# aery32.net
KiCad netlist of a schematic drawn in EAGLE
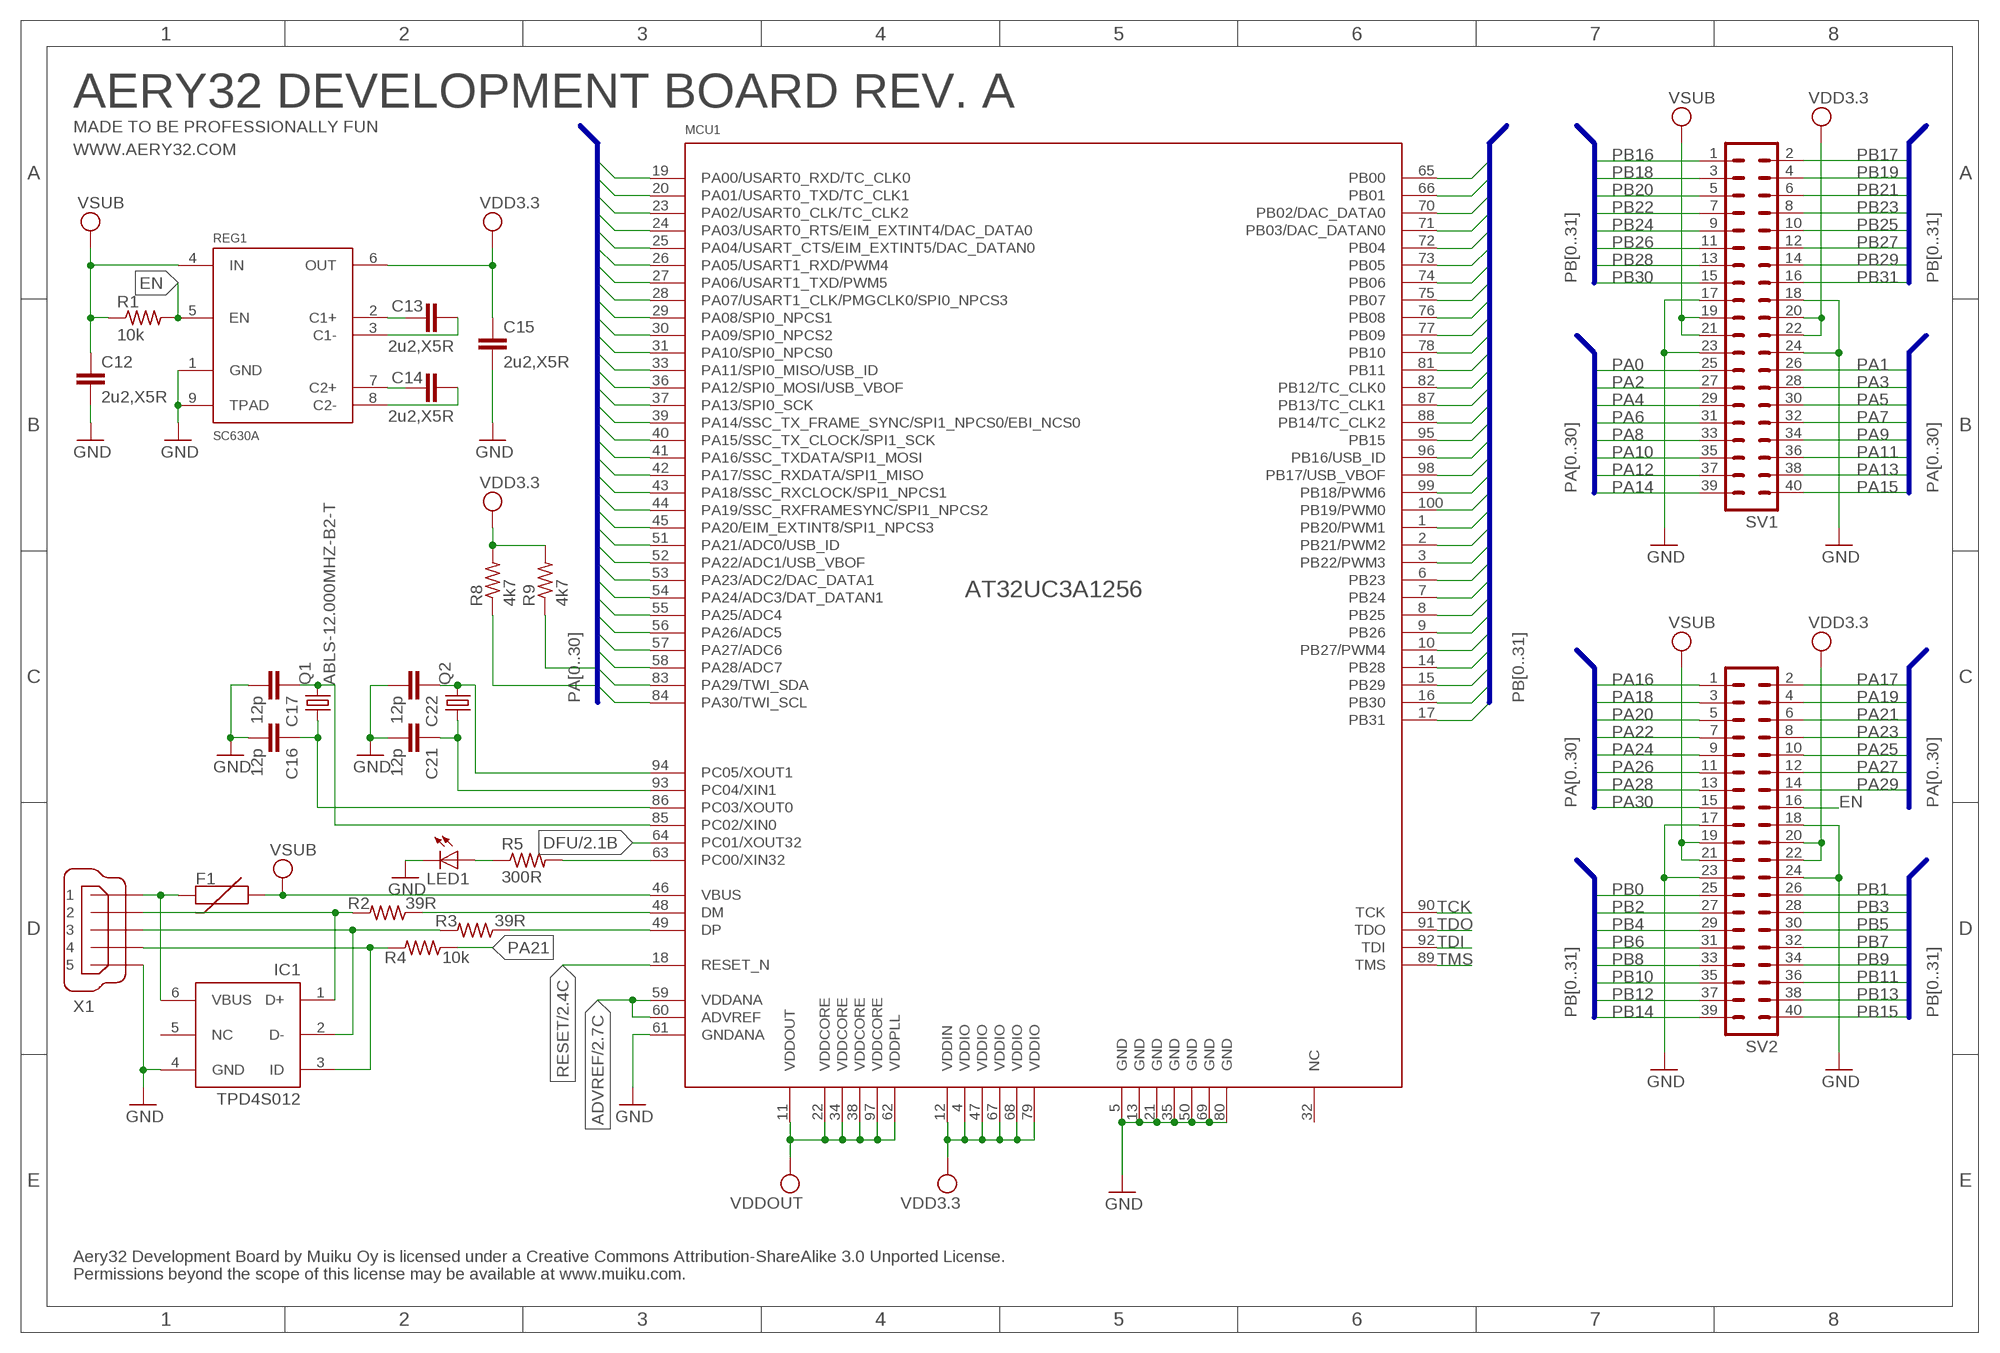
[diagram p0: schematic, sheet 1]
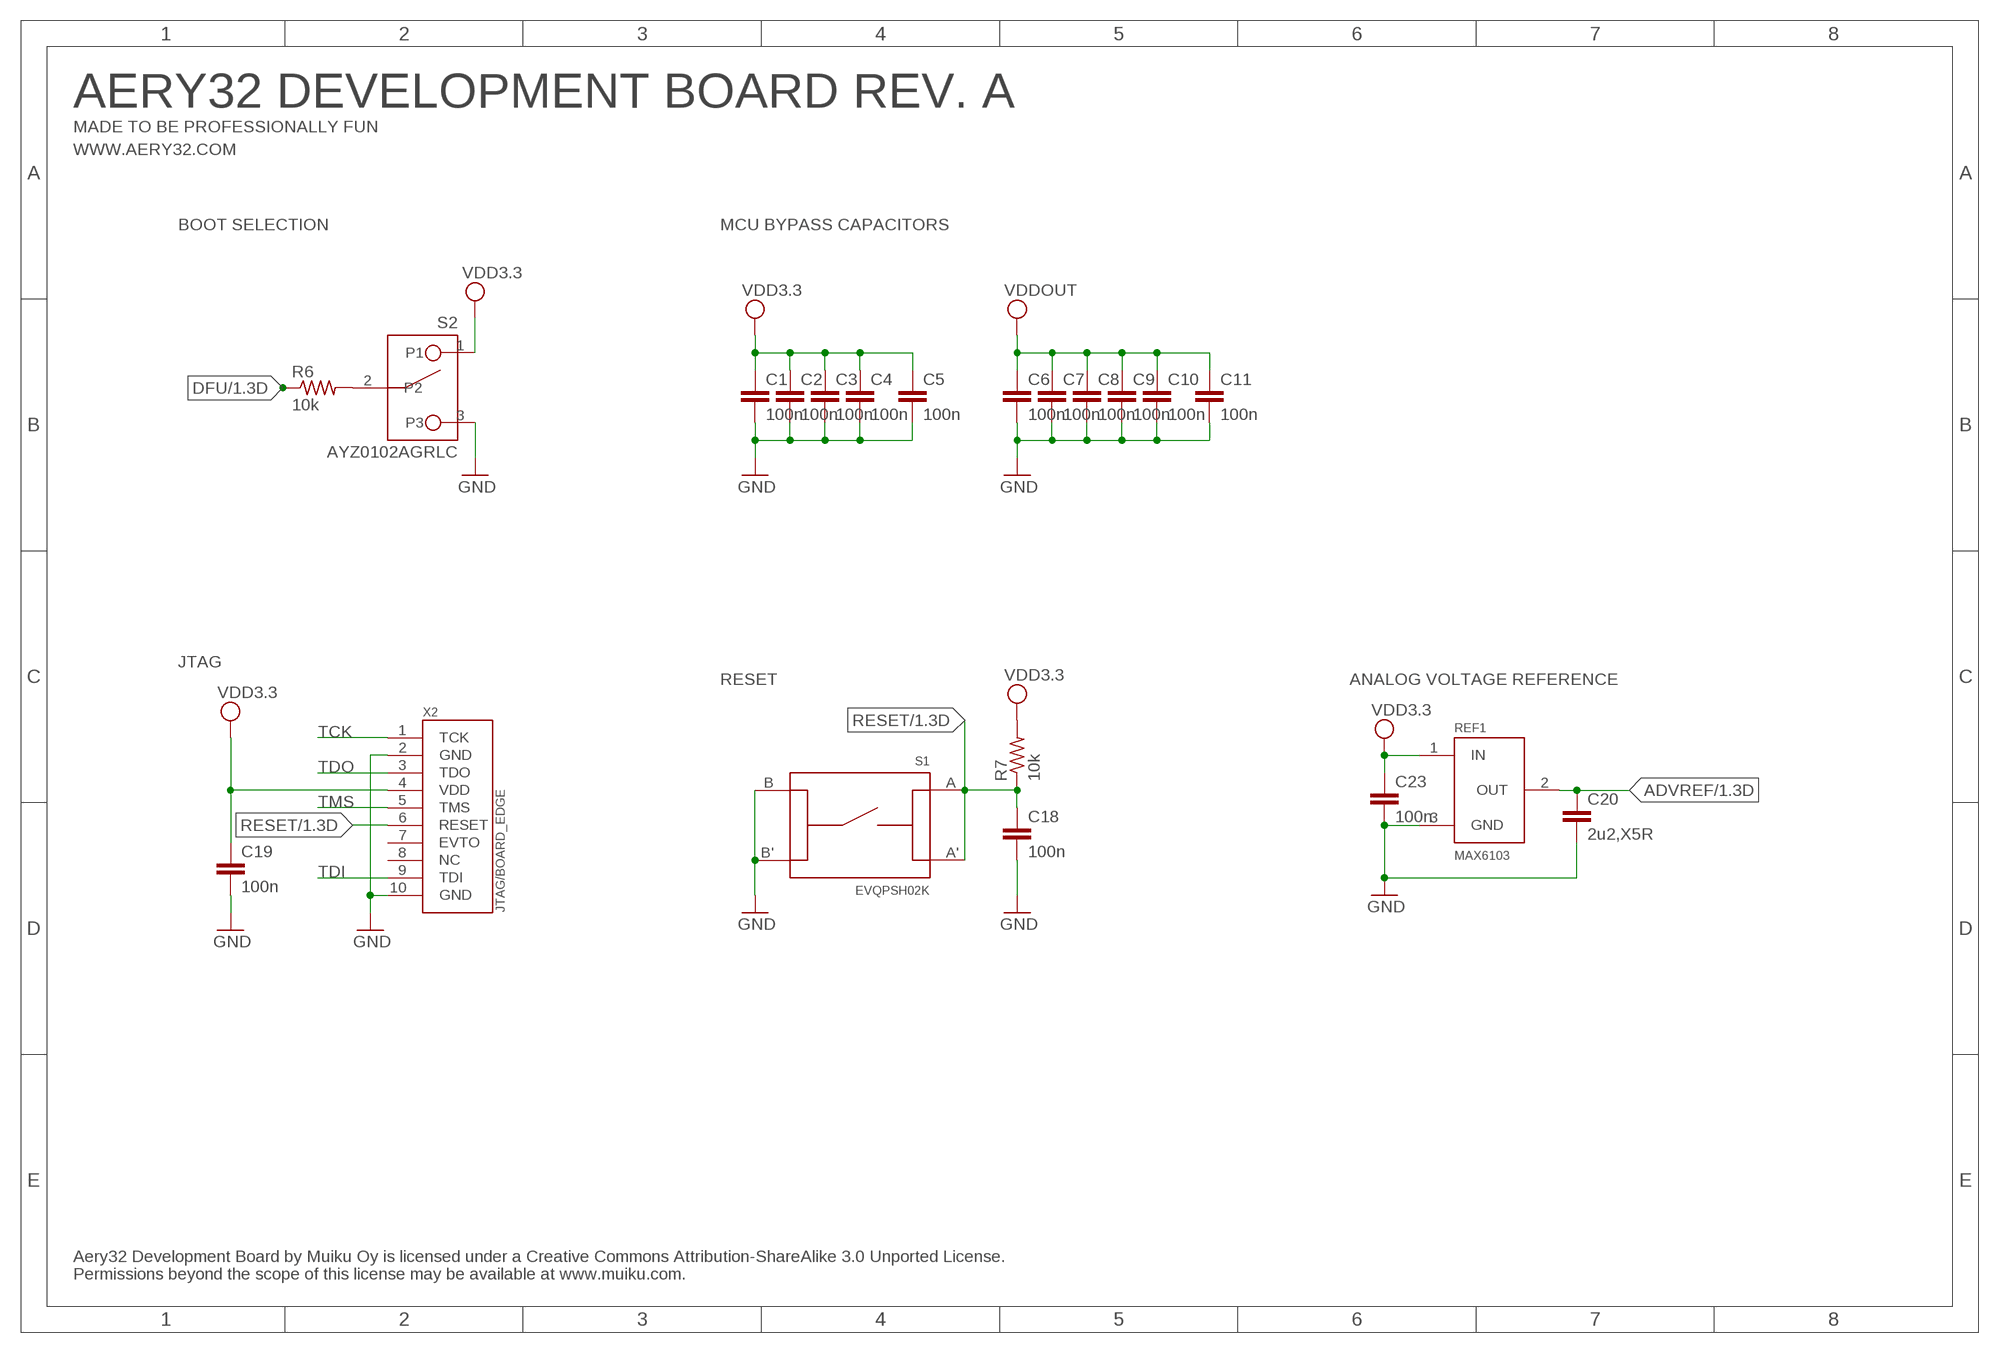
[diagram p1: schematic, sheet 2]

(export (version "E")
  (design (tool "Eeschema 10.0.6"))
  (components
    (comp (ref "C1")
      (value "100n")
      (footprint "eagle-import:C0402")
      (libsource (lib "eagle-import") (part "C-EUC0402"))
    )
    (comp (ref "C2")
      (value "100n")
      (footprint "eagle-import:C0402")
      (libsource (lib "eagle-import") (part "C-EUC0402"))
    )
    (comp (ref "C3")
      (value "100n")
      (footprint "eagle-import:C0402")
      (libsource (lib "eagle-import") (part "C-EUC0402"))
    )
    (comp (ref "C4")
      (value "100n")
      (footprint "eagle-import:C0402")
      (libsource (lib "eagle-import") (part "C-EUC0402"))
    )
    (comp (ref "C5")
      (value "100n")
      (footprint "eagle-import:C0402")
      (libsource (lib "eagle-import") (part "C-EUC0402"))
    )
    (comp (ref "C6")
      (value "100n")
      (footprint "eagle-import:C0402")
      (libsource (lib "eagle-import") (part "C-EUC0402"))
    )
    (comp (ref "C7")
      (value "100n")
      (footprint "eagle-import:C0402")
      (libsource (lib "eagle-import") (part "C-EUC0402"))
    )
    (comp (ref "C8")
      (value "100n")
      (footprint "eagle-import:C0402")
      (libsource (lib "eagle-import") (part "C-EUC0402"))
    )
    (comp (ref "C9")
      (value "100n")
      (footprint "eagle-import:C0402")
      (libsource (lib "eagle-import") (part "C-EUC0402"))
    )
    (comp (ref "C10")
      (value "100n")
      (footprint "eagle-import:C0402")
      (libsource (lib "eagle-import") (part "C-EUC0402"))
    )
    (comp (ref "C11")
      (value "100n")
      (footprint "eagle-import:C0402")
      (libsource (lib "eagle-import") (part "C-EUC0402"))
    )
    (comp (ref "C18")
      (value "100n")
      (footprint "eagle-import:C0402")
      (libsource (lib "eagle-import") (part "C-EUC0402"))
    )
    (comp (ref "C19")
      (value "100n")
      (footprint "eagle-import:C0402")
      (libsource (lib "eagle-import") (part "C-EUC0402"))
    )
    (comp (ref "C20")
      (value "2u2,X5R")
      (footprint "eagle-import:C0402")
      (libsource (lib "eagle-import") (part "C-EUC0402"))
    )
    (comp (ref "C23")
      (value "100n")
      (footprint "eagle-import:C0402")
      (libsource (lib "eagle-import") (part "C-EUC0402"))
    )
    (comp (ref "R6")
      (value "10k")
      (footprint "eagle-import:R0402")
      (libsource (lib "eagle-import") (part "R-US_R0402"))
    )
    (comp (ref "R7")
      (value "10k")
      (footprint "eagle-import:R0402")
      (libsource (lib "eagle-import") (part "R-US_R0402"))
    )
    (comp (ref "REF1")
      (value "MAX6103")
      (footprint "eagle-import:SOT23")
      (libsource (lib "eagle-import") (part "REF3320"))
    )
    (comp (ref "S1")
      (value "EVQPSH02K")
      (footprint "eagle-import:EVQPSH02K")
      (libsource (lib "eagle-import") (part "EVQPSH02K"))
    )
    (comp (ref "S2")
      (value "AYZ0102AGRLC")
      (footprint "eagle-import:AYZ0102AGRLC")
      (libsource (lib "eagle-import") (part "AYZ0102AGRLC"))
    )
    (comp (ref "X2")
      (value "JTAG/BOARD_EDGE")
      (footprint "eagle-import:JTAG_BOARD_EDGE")
      (libsource (lib "eagle-import") (part "JTAG/BOARD_EDGE"))
    )
    (comp (ref "C12")
      (value "2u2,X5R")
      (footprint "eagle-import:C0402")
      (libsource (lib "eagle-import") (part "C-EUC0402"))
    )
    (comp (ref "C13")
      (value "2u2,X5R")
      (footprint "eagle-import:C0402")
      (libsource (lib "eagle-import") (part "C-EUC0402"))
    )
    (comp (ref "C14")
      (value "2u2,X5R")
      (footprint "eagle-import:C0402")
      (libsource (lib "eagle-import") (part "C-EUC0402"))
    )
    (comp (ref "C15")
      (value "2u2,X5R")
      (footprint "eagle-import:C0402")
      (libsource (lib "eagle-import") (part "C-EUC0402"))
    )
    (comp (ref "C16")
      (value "12p")
      (footprint "eagle-import:C0402")
      (libsource (lib "eagle-import") (part "C-EUC0402"))
    )
    (comp (ref "C17")
      (value "12p")
      (footprint "eagle-import:C0402")
      (libsource (lib "eagle-import") (part "C-EUC0402"))
    )
    (comp (ref "C21")
      (value "12p")
      (footprint "eagle-import:C0402")
      (libsource (lib "eagle-import") (part "C-EUC0402"))
    )
    (comp (ref "C22")
      (value "12p")
      (footprint "eagle-import:C0402")
      (libsource (lib "eagle-import") (part "C-EUC0402"))
    )
    (comp (ref "F1")
      (value "PTCSMD")
      (footprint "eagle-import:PTC-1206")
      (libsource (lib "eagle-import") (part "PTCSMD"))
    )
    (comp (ref "IC1")
      (value "TPD4S012")
      (footprint "eagle-import:DRY")
      (libsource (lib "eagle-import") (part "TPD4S012"))
    )
    (comp (ref "LED1")
      (value "LEDCHIPLED_0805")
      (footprint "eagle-import:CHIPLED_0805")
      (libsource (lib "eagle-import") (part "LEDCHIPLED_0805"))
    )
    (comp (ref "MCU1")
      (value "AT32UC3A1256")
      (footprint "eagle-import:TQFP100")
      (fields (field (name "FARNELL") "1841636"))
      (libsource (lib "eagle-import") (part "AT32UC3A1128"))
    )
    (comp (ref "Q1")
      (value "ABLS-12.000MHZ-B2-T")
      (footprint "eagle-import:HC49UP")
      (libsource (lib "eagle-import") (part "CRYSTALHC49UP"))
    )
    (comp (ref "Q2")
      (value "CRYSTALTC38H")
      (footprint "eagle-import:TC38H")
      (libsource (lib "eagle-import") (part "CRYSTALTC38H"))
    )
    (comp (ref "R1")
      (value "10k")
      (footprint "eagle-import:R0402")
      (libsource (lib "eagle-import") (part "R-US_R0402"))
    )
    (comp (ref "R2")
      (value "39R")
      (footprint "eagle-import:R0402")
      (libsource (lib "eagle-import") (part "R-US_R0402"))
    )
    (comp (ref "R3")
      (value "39R")
      (footprint "eagle-import:R0402")
      (libsource (lib "eagle-import") (part "R-US_R0402"))
    )
    (comp (ref "R4")
      (value "10k")
      (footprint "eagle-import:R0402")
      (libsource (lib "eagle-import") (part "R-US_R0402"))
    )
    (comp (ref "R5")
      (value "300R")
      (footprint "eagle-import:R0402")
      (libsource (lib "eagle-import") (part "R-US_R0402"))
    )
    (comp (ref "R8")
      (value "4k7")
      (footprint "eagle-import:R0402")
      (libsource (lib "eagle-import") (part "R-US_R0402"))
    )
    (comp (ref "R9")
      (value "4k7")
      (footprint "eagle-import:R0402")
      (libsource (lib "eagle-import") (part "R-US_R0402"))
    )
    (comp (ref "REG1")
      (value "SC630A")
      (footprint "eagle-import:MLPD-UT-8")
      (libsource (lib "eagle-import") (part "SC630A"))
    )
    (comp (ref "SV1")
      (value "MA20-2")
      (footprint "eagle-import:MA20-2")
      (libsource (lib "eagle-import") (part "MA20-2"))
    )
    (comp (ref "SV2")
      (value "MA20-2")
      (footprint "eagle-import:MA20-2")
      (libsource (lib "eagle-import") (part "MA20-2"))
    )
    (comp (ref "X1")
      (value "USBMINI-B")
      (footprint "eagle-import:MINIUSB")
      (libsource (lib "eagle-import") (part "MINIUSB"))
    )
  )
  (nets
    (net (code "3") (name "ADVREF") (class "Default")
      (node (ref "C20") (pin "1") (pinfunction "1_1") (pintype "passive"))
      (node (ref "MCU1") (pin "59") (pinfunction "VDDANA_59") (pintype "passive"))
      (node (ref "MCU1") (pin "60") (pinfunction "ADVREF_60") (pintype "passive"))
      (node (ref "REF1") (pin "2") (pinfunction "OUT_2") (pintype "passive"))
    )
    (net (code "4") (name "DFU") (class "Default")
      (node (ref "MCU1") (pin "64") (pinfunction "PC01/XOUT32_64") (pintype "bidirectional"))
      (node (ref "R6") (pin "1") (pinfunction "1_1") (pintype "passive"))
    )
    (net (code "5") (name "EN") (class "Default")
      (node (ref "R1") (pin "2") (pinfunction "2_2") (pintype "passive"))
      (node (ref "REG1") (pin "5") (pinfunction "EN_5") (pintype "input"))
      (node (ref "SV2") (pin "16") (pinfunction "16_16") (pintype "passive"))
    )
    (net (code "6") (name "GND") (class "Default")
      (node (ref "C1") (pin "2") (pinfunction "2_2") (pintype "passive"))
      (node (ref "C10") (pin "2") (pinfunction "2_2") (pintype "passive"))
      (node (ref "C11") (pin "2") (pinfunction "2_2") (pintype "passive"))
      (node (ref "C12") (pin "2") (pinfunction "2_2") (pintype "passive"))
      (node (ref "C15") (pin "2") (pinfunction "2_2") (pintype "passive"))
      (node (ref "C16") (pin "2") (pinfunction "2_2") (pintype "passive"))
      (node (ref "C17") (pin "2") (pinfunction "2_2") (pintype "passive"))
      (node (ref "C18") (pin "2") (pinfunction "2_2") (pintype "passive"))
      (node (ref "C19") (pin "2") (pinfunction "2_2") (pintype "passive"))
      (node (ref "C2") (pin "2") (pinfunction "2_2") (pintype "passive"))
      (node (ref "C20") (pin "2") (pinfunction "2_2") (pintype "passive"))
      (node (ref "C21") (pin "2") (pinfunction "2_2") (pintype "passive"))
      (node (ref "C22") (pin "2") (pinfunction "2_2") (pintype "passive"))
      (node (ref "C23") (pin "2") (pinfunction "2_2") (pintype "passive"))
      (node (ref "C3") (pin "2") (pinfunction "2_2") (pintype "passive"))
      (node (ref "C4") (pin "2") (pinfunction "2_2") (pintype "passive"))
      (node (ref "C5") (pin "2") (pinfunction "2_2") (pintype "passive"))
      (node (ref "C6") (pin "2") (pinfunction "2_2") (pintype "passive"))
      (node (ref "C7") (pin "2") (pinfunction "2_2") (pintype "passive"))
      (node (ref "C8") (pin "2") (pinfunction "2_2") (pintype "passive"))
      (node (ref "C9") (pin "2") (pinfunction "2_2") (pintype "passive"))
      (node (ref "IC1") (pin "4") (pinfunction "GND_4") (pintype "passive"))
      (node (ref "LED1") (pin "C") (pinfunction "C_C") (pintype "passive"))
      (node (ref "MCU1") (pin "13") (pinfunction "GND_13") (pintype "power_in"))
      (node (ref "MCU1") (pin "21") (pinfunction "GND_21") (pintype "power_in"))
      (node (ref "MCU1") (pin "35") (pinfunction "GND_35") (pintype "bidirectional"))
      (node (ref "MCU1") (pin "5") (pinfunction "GND_5") (pintype "power_in"))
      (node (ref "MCU1") (pin "50") (pinfunction "GND_50") (pintype "bidirectional"))
      (node (ref "MCU1") (pin "61") (pinfunction "GNDANA_61") (pintype "passive"))
      (node (ref "MCU1") (pin "69") (pinfunction "GND_69") (pintype "power_in"))
      (node (ref "MCU1") (pin "80") (pinfunction "GND_80") (pintype "power_in"))
      (node (ref "REF1") (pin "3") (pinfunction "GND_3") (pintype "passive"))
      (node (ref "REG1") (pin "1") (pinfunction "GND_1") (pintype "passive"))
      (node (ref "REG1") (pin "9") (pinfunction "TPAD_9") (pintype "passive"))
      (node (ref "S1") (pin "B") (pinfunction "B_B") (pintype "passive"))
      (node (ref "S1") (pin "B'") (pinfunction "B'_B'") (pintype "passive"))
      (node (ref "S2") (pin "3") (pinfunction "P3_3") (pintype "passive"))
      (node (ref "SV1") (pin "17") (pinfunction "17_17") (pintype "passive"))
      (node (ref "SV1") (pin "18") (pinfunction "18_18") (pintype "passive"))
      (node (ref "SV1") (pin "23") (pinfunction "23_23") (pintype "passive"))
      (node (ref "SV1") (pin "24") (pinfunction "24_24") (pintype "passive"))
      (node (ref "SV2") (pin "17") (pinfunction "17_17") (pintype "passive"))
      (node (ref "SV2") (pin "18") (pinfunction "18_18") (pintype "passive"))
      (node (ref "SV2") (pin "23") (pinfunction "23_23") (pintype "passive"))
      (node (ref "SV2") (pin "24") (pinfunction "24_24") (pintype "passive"))
      (node (ref "X1") (pin "5") (pinfunction "5_5") (pintype "passive"))
      (node (ref "X2") (pin "10") (pinfunction "GND_10") (pintype "power_in"))
      (node (ref "X2") (pin "2") (pinfunction "GND_2") (pintype "power_in"))
    )
    (net (code "7") (name "Net-(IC1-D+)") (class "Default")
      (node (ref "IC1") (pin "1") (pinfunction "D+_1") (pintype "passive"))
      (node (ref "R2") (pin "2") (pinfunction "2_2") (pintype "passive"))
      (node (ref "X1") (pin "2") (pinfunction "2_2") (pintype "passive"))
    )
    (net (code "8") (name "Net-(IC1-D-)") (class "Default")
      (node (ref "IC1") (pin "2") (pinfunction "D-_2") (pintype "passive"))
      (node (ref "R3") (pin "2") (pinfunction "2_2") (pintype "passive"))
      (node (ref "X1") (pin "3") (pinfunction "3_3") (pintype "passive"))
    )
    (net (code "9") (name "Net-(IC1-ID)") (class "Default")
      (node (ref "IC1") (pin "3") (pinfunction "ID_3") (pintype "passive"))
      (node (ref "R4") (pin "2") (pinfunction "2_2") (pintype "passive"))
      (node (ref "X1") (pin "4") (pinfunction "4_4") (pintype "passive"))
    )
    (net (code "10") (name "Net-(IC1-VBUS)") (class "Default")
      (node (ref "F1") (pin "2") (pinfunction "2_2") (pintype "bidirectional"))
      (node (ref "IC1") (pin "6") (pinfunction "VBUS_6") (pintype "passive"))
      (node (ref "X1") (pin "1") (pinfunction "1_1") (pintype "passive"))
    )
    (net (code "11") (name "Net-(LED1-PadA)") (class "Default")
      (node (ref "LED1") (pin "A") (pinfunction "A_A") (pintype "passive"))
      (node (ref "R5") (pin "1") (pinfunction "1_1") (pintype "passive"))
    )
    (net (code "12") (name "Net-(MCU1-DM)") (class "Default")
      (node (ref "MCU1") (pin "48") (pinfunction "DM_48") (pintype "bidirectional"))
      (node (ref "R2") (pin "1") (pinfunction "1_1") (pintype "passive"))
    )
    (net (code "13") (name "Net-(MCU1-DP)") (class "Default")
      (node (ref "MCU1") (pin "49") (pinfunction "DP_49") (pintype "bidirectional"))
      (node (ref "R3") (pin "1") (pinfunction "1_1") (pintype "passive"))
    )
    (net (code "14") (name "Net-(MCU1-PC00{slash}XIN32)") (class "Default")
      (node (ref "MCU1") (pin "63") (pinfunction "PC00/XIN32_63") (pintype "bidirectional"))
      (node (ref "R5") (pin "2") (pinfunction "2_2") (pintype "passive"))
    )
    (net (code "15") (name "Net-(MCU1-PC02{slash}XIN0)") (class "Default")
      (node (ref "C17") (pin "1") (pinfunction "1_1") (pintype "passive"))
      (node (ref "MCU1") (pin "85") (pinfunction "PC02/XIN0_85") (pintype "bidirectional"))
      (node (ref "Q1") (pin "2") (pinfunction "2_2") (pintype "passive"))
    )
    (net (code "16") (name "Net-(MCU1-PC03{slash}XOUT0)") (class "Default")
      (node (ref "C16") (pin "1") (pinfunction "1_1") (pintype "passive"))
      (node (ref "MCU1") (pin "86") (pinfunction "PC03/XOUT0_86") (pintype "bidirectional"))
      (node (ref "Q1") (pin "1") (pinfunction "1_1") (pintype "passive"))
    )
    (net (code "17") (name "Net-(MCU1-PC04{slash}XIN1)") (class "Default")
      (node (ref "C21") (pin "1") (pinfunction "1_1") (pintype "passive"))
      (node (ref "MCU1") (pin "93") (pinfunction "PC04/XIN1_93") (pintype "bidirectional"))
      (node (ref "Q2") (pin "1") (pinfunction "1_1") (pintype "passive"))
    )
    (net (code "18") (name "Net-(MCU1-PC05{slash}XOUT1)") (class "Default")
      (node (ref "C22") (pin "1") (pinfunction "1_1") (pintype "passive"))
      (node (ref "MCU1") (pin "94") (pinfunction "PC05/XOUT1_94") (pintype "bidirectional"))
      (node (ref "Q2") (pin "2") (pinfunction "2_2") (pintype "passive"))
    )
    (net (code "19") (name "Net-(REG1-C1+)") (class "Default")
      (node (ref "C13") (pin "1") (pinfunction "1_1") (pintype "passive"))
      (node (ref "REG1") (pin "2") (pinfunction "C1+_2") (pintype "passive"))
    )
    (net (code "20") (name "Net-(REG1-C1-)") (class "Default")
      (node (ref "C13") (pin "2") (pinfunction "2_2") (pintype "passive"))
      (node (ref "REG1") (pin "3") (pinfunction "C1-_3") (pintype "passive"))
    )
    (net (code "21") (name "Net-(REG1-C2+)") (class "Default")
      (node (ref "C14") (pin "1") (pinfunction "1_1") (pintype "passive"))
      (node (ref "REG1") (pin "7") (pinfunction "C2+_7") (pintype "passive"))
    )
    (net (code "22") (name "Net-(REG1-C2-)") (class "Default")
      (node (ref "C14") (pin "2") (pinfunction "2_2") (pintype "passive"))
      (node (ref "REG1") (pin "8") (pinfunction "C2-_8") (pintype "passive"))
    )
    (net (code "23") (name "Net-(S2-P2)") (class "Default")
      (node (ref "R6") (pin "2") (pinfunction "2_2") (pintype "passive"))
      (node (ref "S2") (pin "2") (pinfunction "P2_2") (pintype "passive"))
    )
    (net (code "24") (name "PA0") (class "Default")
      (node (ref "MCU1") (pin "19") (pinfunction "PA00/USART0_RXD/TC_CLK0_19") (pintype "bidirectional"))
      (node (ref "SV1") (pin "25") (pinfunction "25_25") (pintype "passive"))
    )
    (net (code "25") (name "PA1") (class "Default")
      (node (ref "MCU1") (pin "20") (pinfunction "PA01/USART0_TXD/TC_CLK1_20") (pintype "bidirectional"))
      (node (ref "SV1") (pin "26") (pinfunction "26_26") (pintype "passive"))
    )
    (net (code "26") (name "PA2") (class "Default")
      (node (ref "MCU1") (pin "23") (pinfunction "PA02/USART0_CLK/TC_CLK2_23") (pintype "bidirectional"))
      (node (ref "SV1") (pin "27") (pinfunction "27_27") (pintype "passive"))
    )
    (net (code "27") (name "PA3") (class "Default")
      (node (ref "MCU1") (pin "24") (pinfunction "PA03/USART0_RTS/EIM_EXTINT4/DAC_DATA0_24") (pintype "bidirectional"))
      (node (ref "SV1") (pin "28") (pinfunction "28_28") (pintype "passive"))
    )
    (net (code "28") (name "PA4") (class "Default")
      (node (ref "MCU1") (pin "25") (pinfunction "PA04/USART_CTS/EIM_EXTINT5/DAC_DATAN0_25") (pintype "bidirectional"))
      (node (ref "SV1") (pin "29") (pinfunction "29_29") (pintype "passive"))
    )
    (net (code "29") (name "PA5") (class "Default")
      (node (ref "MCU1") (pin "26") (pinfunction "PA05/USART1_RXD/PWM4_26") (pintype "bidirectional"))
      (node (ref "SV1") (pin "30") (pinfunction "30_30") (pintype "passive"))
    )
    (net (code "30") (name "PA6") (class "Default")
      (node (ref "MCU1") (pin "27") (pinfunction "PA06/USART1_TXD/PWM5_27") (pintype "bidirectional"))
      (node (ref "SV1") (pin "31") (pinfunction "31_31") (pintype "passive"))
    )
    (net (code "31") (name "PA7") (class "Default")
      (node (ref "MCU1") (pin "28") (pinfunction "PA07/USART1_CLK/PMGCLK0/SPI0_NPCS3_28") (pintype "bidirectional"))
      (node (ref "SV1") (pin "32") (pinfunction "32_32") (pintype "passive"))
    )
    (net (code "32") (name "PA8") (class "Default")
      (node (ref "MCU1") (pin "29") (pinfunction "PA08/SPI0_NPCS1_29") (pintype "bidirectional"))
      (node (ref "SV1") (pin "33") (pinfunction "33_33") (pintype "passive"))
    )
    (net (code "33") (name "PA9") (class "Default")
      (node (ref "MCU1") (pin "30") (pinfunction "PA09/SPI0_NPCS2_30") (pintype "bidirectional"))
      (node (ref "SV1") (pin "34") (pinfunction "34_34") (pintype "passive"))
    )
    (net (code "34") (name "PA10") (class "Default")
      (node (ref "MCU1") (pin "31") (pinfunction "PA10/SPI0_NPCS0_31") (pintype "bidirectional"))
      (node (ref "SV1") (pin "35") (pinfunction "35_35") (pintype "passive"))
    )
    (net (code "35") (name "PA11") (class "Default")
      (node (ref "MCU1") (pin "33") (pinfunction "PA11/SPI0_MISO/USB_ID_33") (pintype "bidirectional"))
      (node (ref "SV1") (pin "36") (pinfunction "36_36") (pintype "passive"))
    )
    (net (code "36") (name "PA12") (class "Default")
      (node (ref "MCU1") (pin "36") (pinfunction "PA12/SPI0_MOSI/USB_VBOF_36") (pintype "bidirectional"))
      (node (ref "SV1") (pin "37") (pinfunction "37_37") (pintype "passive"))
    )
    (net (code "37") (name "PA13") (class "Default")
      (node (ref "MCU1") (pin "37") (pinfunction "PA13/SPI0_SCK_37") (pintype "bidirectional"))
      (node (ref "SV1") (pin "38") (pinfunction "38_38") (pintype "passive"))
    )
    (net (code "38") (name "PA14") (class "Default")
      (node (ref "MCU1") (pin "39") (pinfunction "PA14/SSC_TX_FRAME_SYNC/SPI1_NPCS0/EBI_NCS0_39") (pintype "bidirectional"))
      (node (ref "SV1") (pin "39") (pinfunction "39_39") (pintype "passive"))
    )
    (net (code "39") (name "PA15") (class "Default")
      (node (ref "MCU1") (pin "40") (pinfunction "PA15/SSC_TX_CLOCK/SPI1_SCK_40") (pintype "bidirectional"))
      (node (ref "SV1") (pin "40") (pinfunction "40_40") (pintype "passive"))
    )
    (net (code "40") (name "PA16") (class "Default")
      (node (ref "MCU1") (pin "41") (pinfunction "PA16/SSC_TXDATA/SPI1_MOSI_41") (pintype "bidirectional"))
      (node (ref "SV2") (pin "1") (pinfunction "1_1") (pintype "passive"))
    )
    (net (code "41") (name "PA17") (class "Default")
      (node (ref "MCU1") (pin "42") (pinfunction "PA17/SSC_RXDATA/SPI1_MISO_42") (pintype "bidirectional"))
      (node (ref "SV2") (pin "2") (pinfunction "2_2") (pintype "passive"))
    )
    (net (code "42") (name "PA18") (class "Default")
      (node (ref "MCU1") (pin "43") (pinfunction "PA18/SSC_RXCLOCK/SPI1_NPCS1_43") (pintype "bidirectional"))
      (node (ref "SV2") (pin "3") (pinfunction "3_3") (pintype "passive"))
    )
    (net (code "43") (name "PA19") (class "Default")
      (node (ref "MCU1") (pin "44") (pinfunction "PA19/SSC_RXFRAMESYNC/SPI1_NPCS2_44") (pintype "bidirectional"))
      (node (ref "SV2") (pin "4") (pinfunction "4_4") (pintype "passive"))
    )
    (net (code "44") (name "PA20") (class "Default")
      (node (ref "MCU1") (pin "45") (pinfunction "PA20/EIM_EXTINT8/SPI1_NPCS3_45") (pintype "bidirectional"))
      (node (ref "SV2") (pin "5") (pinfunction "5_5") (pintype "passive"))
    )
    (net (code "45") (name "PA21") (class "Default")
      (node (ref "MCU1") (pin "51") (pinfunction "PA21/ADC0/USB_ID_51") (pintype "bidirectional"))
      (node (ref "R4") (pin "1") (pinfunction "1_1") (pintype "passive"))
      (node (ref "SV2") (pin "6") (pinfunction "6_6") (pintype "passive"))
    )
    (net (code "46") (name "PA22") (class "Default")
      (node (ref "MCU1") (pin "52") (pinfunction "PA22/ADC1/USB_VBOF_52") (pintype "bidirectional"))
      (node (ref "SV2") (pin "7") (pinfunction "7_7") (pintype "passive"))
    )
    (net (code "47") (name "PA23") (class "Default")
      (node (ref "MCU1") (pin "53") (pinfunction "PA23/ADC2/DAC_DATA1_53") (pintype "bidirectional"))
      (node (ref "SV2") (pin "8") (pinfunction "8_8") (pintype "passive"))
    )
    (net (code "48") (name "PA24") (class "Default")
      (node (ref "MCU1") (pin "54") (pinfunction "PA24/ADC3/DAT_DATAN1_54") (pintype "bidirectional"))
      (node (ref "SV2") (pin "9") (pinfunction "9_9") (pintype "passive"))
    )
    (net (code "49") (name "PA25") (class "Default")
      (node (ref "MCU1") (pin "55") (pinfunction "PA25/ADC4_55") (pintype "bidirectional"))
      (node (ref "SV2") (pin "10") (pinfunction "10_10") (pintype "passive"))
    )
    (net (code "50") (name "PA26") (class "Default")
      (node (ref "MCU1") (pin "56") (pinfunction "PA26/ADC5_56") (pintype "bidirectional"))
      (node (ref "SV2") (pin "11") (pinfunction "11_11") (pintype "passive"))
    )
    (net (code "51") (name "PA27") (class "Default")
      (node (ref "MCU1") (pin "57") (pinfunction "PA27/ADC6_57") (pintype "bidirectional"))
      (node (ref "SV2") (pin "12") (pinfunction "12_12") (pintype "passive"))
    )
    (net (code "52") (name "PA28") (class "Default")
      (node (ref "MCU1") (pin "58") (pinfunction "PA28/ADC7_58") (pintype "bidirectional"))
      (node (ref "SV2") (pin "13") (pinfunction "13_13") (pintype "passive"))
    )
    (net (code "53") (name "PA29") (class "Default")
      (node (ref "MCU1") (pin "83") (pinfunction "PA29/TWI_SDA_83") (pintype "bidirectional"))
      (node (ref "R9") (pin "1") (pinfunction "1_1") (pintype "passive"))
      (node (ref "SV2") (pin "14") (pinfunction "14_14") (pintype "passive"))
    )
    (net (code "54") (name "PA30") (class "Default")
      (node (ref "MCU1") (pin "84") (pinfunction "PA30/TWI_SCL_84") (pintype "bidirectional"))
      (node (ref "R8") (pin "1") (pinfunction "1_1") (pintype "passive"))
      (node (ref "SV2") (pin "15") (pinfunction "15_15") (pintype "passive"))
    )
    (net (code "55") (name "PB0") (class "Default")
      (node (ref "MCU1") (pin "65") (pinfunction "PB00_65") (pintype "bidirectional"))
      (node (ref "SV2") (pin "25") (pinfunction "25_25") (pintype "passive"))
    )
    (net (code "56") (name "PB1") (class "Default")
      (node (ref "MCU1") (pin "66") (pinfunction "PB01_66") (pintype "bidirectional"))
      (node (ref "SV2") (pin "26") (pinfunction "26_26") (pintype "passive"))
    )
    (net (code "57") (name "PB2") (class "Default")
      (node (ref "MCU1") (pin "70") (pinfunction "PB02/DAC_DATA0_70") (pintype "bidirectional"))
      (node (ref "SV2") (pin "27") (pinfunction "27_27") (pintype "passive"))
    )
    (net (code "58") (name "PB3") (class "Default")
      (node (ref "MCU1") (pin "71") (pinfunction "PB03/DAC_DATAN0_71") (pintype "bidirectional"))
      (node (ref "SV2") (pin "28") (pinfunction "28_28") (pintype "passive"))
    )
    (net (code "59") (name "PB4") (class "Default")
      (node (ref "MCU1") (pin "72") (pinfunction "PB04_72") (pintype "bidirectional"))
      (node (ref "SV2") (pin "29") (pinfunction "29_29") (pintype "passive"))
    )
    (net (code "60") (name "PB5") (class "Default")
      (node (ref "MCU1") (pin "73") (pinfunction "PB05_73") (pintype "bidirectional"))
      (node (ref "SV2") (pin "30") (pinfunction "30_30") (pintype "passive"))
    )
    (net (code "61") (name "PB6") (class "Default")
      (node (ref "MCU1") (pin "74") (pinfunction "PB06_74") (pintype "bidirectional"))
      (node (ref "SV2") (pin "31") (pinfunction "31_31") (pintype "passive"))
    )
    (net (code "62") (name "PB7") (class "Default")
      (node (ref "MCU1") (pin "75") (pinfunction "PB07_75") (pintype "bidirectional"))
      (node (ref "SV2") (pin "32") (pinfunction "32_32") (pintype "passive"))
    )
    (net (code "63") (name "PB8") (class "Default")
      (node (ref "MCU1") (pin "76") (pinfunction "PB08_76") (pintype "bidirectional"))
      (node (ref "SV2") (pin "33") (pinfunction "33_33") (pintype "passive"))
    )
    (net (code "64") (name "PB9") (class "Default")
      (node (ref "MCU1") (pin "77") (pinfunction "PB09_77") (pintype "bidirectional"))
      (node (ref "SV2") (pin "34") (pinfunction "34_34") (pintype "passive"))
    )
    (net (code "65") (name "PB10") (class "Default")
      (node (ref "MCU1") (pin "78") (pinfunction "PB10_78") (pintype "bidirectional"))
      (node (ref "SV2") (pin "35") (pinfunction "35_35") (pintype "passive"))
    )
    (net (code "66") (name "PB11") (class "Default")
      (node (ref "MCU1") (pin "81") (pinfunction "PB11_81") (pintype "bidirectional"))
      (node (ref "SV2") (pin "36") (pinfunction "36_36") (pintype "passive"))
    )
    (net (code "67") (name "PB12") (class "Default")
      (node (ref "MCU1") (pin "82") (pinfunction "PB12/TC_CLK0_82") (pintype "bidirectional"))
      (node (ref "SV2") (pin "37") (pinfunction "37_37") (pintype "passive"))
    )
    (net (code "68") (name "PB13") (class "Default")
      (node (ref "MCU1") (pin "87") (pinfunction "PB13/TC_CLK1_87") (pintype "bidirectional"))
      (node (ref "SV2") (pin "38") (pinfunction "38_38") (pintype "passive"))
    )
    (net (code "69") (name "PB14") (class "Default")
      (node (ref "MCU1") (pin "88") (pinfunction "PB14/TC_CLK2_88") (pintype "bidirectional"))
      (node (ref "SV2") (pin "39") (pinfunction "39_39") (pintype "passive"))
    )
    (net (code "70") (name "PB15") (class "Default")
      (node (ref "MCU1") (pin "95") (pinfunction "PB15_95") (pintype "bidirectional"))
      (node (ref "SV2") (pin "40") (pinfunction "40_40") (pintype "passive"))
    )
    (net (code "71") (name "PB16") (class "Default")
      (node (ref "MCU1") (pin "96") (pinfunction "PB16/USB_ID_96") (pintype "bidirectional"))
      (node (ref "SV1") (pin "1") (pinfunction "1_1") (pintype "passive"))
    )
    (net (code "72") (name "PB17") (class "Default")
      (node (ref "MCU1") (pin "98") (pinfunction "PB17/USB_VBOF_98") (pintype "bidirectional"))
      (node (ref "SV1") (pin "2") (pinfunction "2_2") (pintype "passive"))
    )
    (net (code "73") (name "PB18") (class "Default")
      (node (ref "MCU1") (pin "99") (pinfunction "PB18/PWM6_99") (pintype "bidirectional"))
      (node (ref "SV1") (pin "3") (pinfunction "3_3") (pintype "passive"))
    )
    (net (code "74") (name "PB19") (class "Default")
      (node (ref "MCU1") (pin "100") (pinfunction "PB19/PWM0_100") (pintype "bidirectional"))
      (node (ref "SV1") (pin "4") (pinfunction "4_4") (pintype "passive"))
    )
    (net (code "75") (name "PB20") (class "Default")
      (node (ref "MCU1") (pin "1") (pinfunction "PB20/PWM1_1") (pintype "bidirectional"))
      (node (ref "SV1") (pin "5") (pinfunction "5_5") (pintype "passive"))
    )
    (net (code "76") (name "PB21") (class "Default")
      (node (ref "MCU1") (pin "2") (pinfunction "PB21/PWM2_2") (pintype "bidirectional"))
      (node (ref "SV1") (pin "6") (pinfunction "6_6") (pintype "passive"))
    )
    (net (code "77") (name "PB22") (class "Default")
      (node (ref "MCU1") (pin "3") (pinfunction "PB22/PWM3_3") (pintype "bidirectional"))
      (node (ref "SV1") (pin "7") (pinfunction "7_7") (pintype "passive"))
    )
    (net (code "78") (name "PB23") (class "Default")
      (node (ref "MCU1") (pin "6") (pinfunction "PB23_6") (pintype "bidirectional"))
      (node (ref "SV1") (pin "8") (pinfunction "8_8") (pintype "passive"))
    )
    (net (code "79") (name "PB24") (class "Default")
      (node (ref "MCU1") (pin "7") (pinfunction "PB24_7") (pintype "bidirectional"))
      (node (ref "SV1") (pin "9") (pinfunction "9_9") (pintype "passive"))
    )
    (net (code "80") (name "PB25") (class "Default")
      (node (ref "MCU1") (pin "8") (pinfunction "PB25_8") (pintype "bidirectional"))
      (node (ref "SV1") (pin "10") (pinfunction "10_10") (pintype "passive"))
    )
    (net (code "81") (name "PB26") (class "Default")
      (node (ref "MCU1") (pin "9") (pinfunction "PB26_9") (pintype "bidirectional"))
      (node (ref "SV1") (pin "11") (pinfunction "11_11") (pintype "passive"))
    )
    (net (code "82") (name "PB27") (class "Default")
      (node (ref "MCU1") (pin "10") (pinfunction "PB27/PWM4_10") (pintype "bidirectional"))
      (node (ref "SV1") (pin "12") (pinfunction "12_12") (pintype "passive"))
    )
    (net (code "83") (name "PB28") (class "Default")
      (node (ref "MCU1") (pin "14") (pinfunction "PB28_14") (pintype "bidirectional"))
      (node (ref "SV1") (pin "13") (pinfunction "13_13") (pintype "passive"))
    )
    (net (code "84") (name "PB29") (class "Default")
      (node (ref "MCU1") (pin "15") (pinfunction "PB29_15") (pintype "bidirectional"))
      (node (ref "SV1") (pin "14") (pinfunction "14_14") (pintype "passive"))
    )
    (net (code "85") (name "PB30") (class "Default")
      (node (ref "MCU1") (pin "16") (pinfunction "PB30_16") (pintype "bidirectional"))
      (node (ref "SV1") (pin "15") (pinfunction "15_15") (pintype "passive"))
    )
    (net (code "86") (name "PB31") (class "Default")
      (node (ref "MCU1") (pin "17") (pinfunction "PB31_17") (pintype "bidirectional"))
      (node (ref "SV1") (pin "16") (pinfunction "16_16") (pintype "passive"))
    )
    (net (code "87") (name "RESET") (class "Default")
      (node (ref "C18") (pin "1") (pinfunction "1_1") (pintype "passive"))
      (node (ref "MCU1") (pin "18") (pinfunction "RESET_N_18") (pintype "bidirectional"))
      (node (ref "R7") (pin "1") (pinfunction "1_1") (pintype "passive"))
      (node (ref "S1") (pin "A") (pinfunction "A_A") (pintype "passive"))
      (node (ref "S1") (pin "A'") (pinfunction "A'_A'") (pintype "passive"))
      (node (ref "X2") (pin "6") (pinfunction "RESET_6") (pintype "bidirectional"))
    )
    (net (code "88") (name "TCK") (class "Default")
      (node (ref "MCU1") (pin "90") (pinfunction "TCK_90") (pintype "bidirectional"))
      (node (ref "X2") (pin "1") (pinfunction "TCK_1") (pintype "bidirectional"))
    )
    (net (code "89") (name "TDI") (class "Default")
      (node (ref "MCU1") (pin "92") (pinfunction "TDI_92") (pintype "bidirectional"))
      (node (ref "X2") (pin "9") (pinfunction "TDI_9") (pintype "bidirectional"))
    )
    (net (code "90") (name "TDO") (class "Default")
      (node (ref "MCU1") (pin "91") (pinfunction "TDO_91") (pintype "bidirectional"))
      (node (ref "X2") (pin "3") (pinfunction "TDO_3") (pintype "bidirectional"))
    )
    (net (code "91") (name "TMS") (class "Default")
      (node (ref "MCU1") (pin "89") (pinfunction "TMS_89") (pintype "bidirectional"))
      (node (ref "X2") (pin "5") (pinfunction "TMS_5") (pintype "bidirectional"))
    )
    (net (code "92") (name "VBUS") (class "Default")
      (node (ref "C12") (pin "1") (pinfunction "1_1") (pintype "passive"))
      (node (ref "F1") (pin "1") (pinfunction "1_1") (pintype "bidirectional"))
      (node (ref "MCU1") (pin "46") (pinfunction "VBUS_46") (pintype "passive"))
      (node (ref "R1") (pin "1") (pinfunction "1_1") (pintype "passive"))
      (node (ref "REG1") (pin "4") (pinfunction "IN_4") (pintype "passive"))
      (node (ref "SV1") (pin "19") (pinfunction "19_19") (pintype "passive"))
      (node (ref "SV1") (pin "21") (pinfunction "21_21") (pintype "passive"))
      (node (ref "SV2") (pin "19") (pinfunction "19_19") (pintype "passive"))
      (node (ref "SV2") (pin "21") (pinfunction "21_21") (pintype "passive"))
    )
    (net (code "93") (name "VDD3.3") (class "Default")
      (node (ref "C1") (pin "1") (pinfunction "1_1") (pintype "passive"))
      (node (ref "C15") (pin "1") (pinfunction "1_1") (pintype "passive"))
      (node (ref "C19") (pin "1") (pinfunction "1_1") (pintype "passive"))
      (node (ref "C2") (pin "1") (pinfunction "1_1") (pintype "passive"))
      (node (ref "C23") (pin "1") (pinfunction "1_1") (pintype "passive"))
      (node (ref "C3") (pin "1") (pinfunction "1_1") (pintype "passive"))
      (node (ref "C4") (pin "1") (pinfunction "1_1") (pintype "passive"))
      (node (ref "C5") (pin "1") (pinfunction "1_1") (pintype "passive"))
      (node (ref "MCU1") (pin "12") (pinfunction "VDDIN_12") (pintype "passive"))
      (node (ref "MCU1") (pin "4") (pinfunction "VDDIO_4") (pintype "passive"))
      (node (ref "MCU1") (pin "47") (pinfunction "VDDIO_47") (pintype "passive"))
      (node (ref "MCU1") (pin "67") (pinfunction "VDDIO_67") (pintype "passive"))
      (node (ref "MCU1") (pin "68") (pinfunction "VDDIO_68") (pintype "passive"))
      (node (ref "MCU1") (pin "79") (pinfunction "VDDIO_79") (pintype "passive"))
      (node (ref "R7") (pin "2") (pinfunction "2_2") (pintype "passive"))
      (node (ref "R8") (pin "2") (pinfunction "2_2") (pintype "passive"))
      (node (ref "R9") (pin "2") (pinfunction "2_2") (pintype "passive"))
      (node (ref "REF1") (pin "1") (pinfunction "IN_1") (pintype "passive"))
      (node (ref "REG1") (pin "6") (pinfunction "OUT_6") (pintype "passive"))
      (node (ref "S2") (pin "1") (pinfunction "P1_1") (pintype "passive"))
      (node (ref "SV1") (pin "20") (pinfunction "20_20") (pintype "passive"))
      (node (ref "SV1") (pin "22") (pinfunction "22_22") (pintype "passive"))
      (node (ref "SV2") (pin "20") (pinfunction "20_20") (pintype "passive"))
      (node (ref "SV2") (pin "22") (pinfunction "22_22") (pintype "passive"))
      (node (ref "X2") (pin "4") (pinfunction "VDD_4") (pintype "power_in"))
    )
    (net (code "94") (name "VDDOUT") (class "Default")
      (node (ref "C10") (pin "1") (pinfunction "1_1") (pintype "passive"))
      (node (ref "C11") (pin "1") (pinfunction "1_1") (pintype "passive"))
      (node (ref "C6") (pin "1") (pinfunction "1_1") (pintype "passive"))
      (node (ref "C7") (pin "1") (pinfunction "1_1") (pintype "passive"))
      (node (ref "C8") (pin "1") (pinfunction "1_1") (pintype "passive"))
      (node (ref "C9") (pin "1") (pinfunction "1_1") (pintype "passive"))
      (node (ref "MCU1") (pin "11") (pinfunction "VDDOUT_11") (pintype "passive"))
      (node (ref "MCU1") (pin "22") (pinfunction "VDDCORE_22") (pintype "passive"))
      (node (ref "MCU1") (pin "34") (pinfunction "VDDCORE_34") (pintype "passive"))
      (node (ref "MCU1") (pin "38") (pinfunction "VDDCORE_38") (pintype "passive"))
      (node (ref "MCU1") (pin "62") (pinfunction "VDDPLL_62") (pintype "passive"))
      (node (ref "MCU1") (pin "97") (pinfunction "VDDCORE_97") (pintype "passive"))
    )
    (net (code "95") (name "unconnected-(IC1-NC-Pad5)") (class "Default")
      (node (ref "IC1") (pin "5") (pinfunction "NC_5") (pintype "no_connect"))
    )
    (net (code "96") (name "unconnected-(MCU1-NC-Pad32)") (class "Default")
      (node (ref "MCU1") (pin "32") (pinfunction "NC_32") (pintype "bidirectional"))
    )
    (net (code "97") (name "unconnected-(X2-EVTO-Pad7)") (class "Default")
      (node (ref "X2") (pin "7") (pinfunction "EVTO_7") (pintype "bidirectional"))
    )
    (net (code "98") (name "unconnected-(X2-NC-Pad8)") (class "Default")
      (node (ref "X2") (pin "8") (pinfunction "NC_8") (pintype "bidirectional"))
    )
  )
)
